# Timer.net
KiCad netlist of a schematic drawn in EAGLE
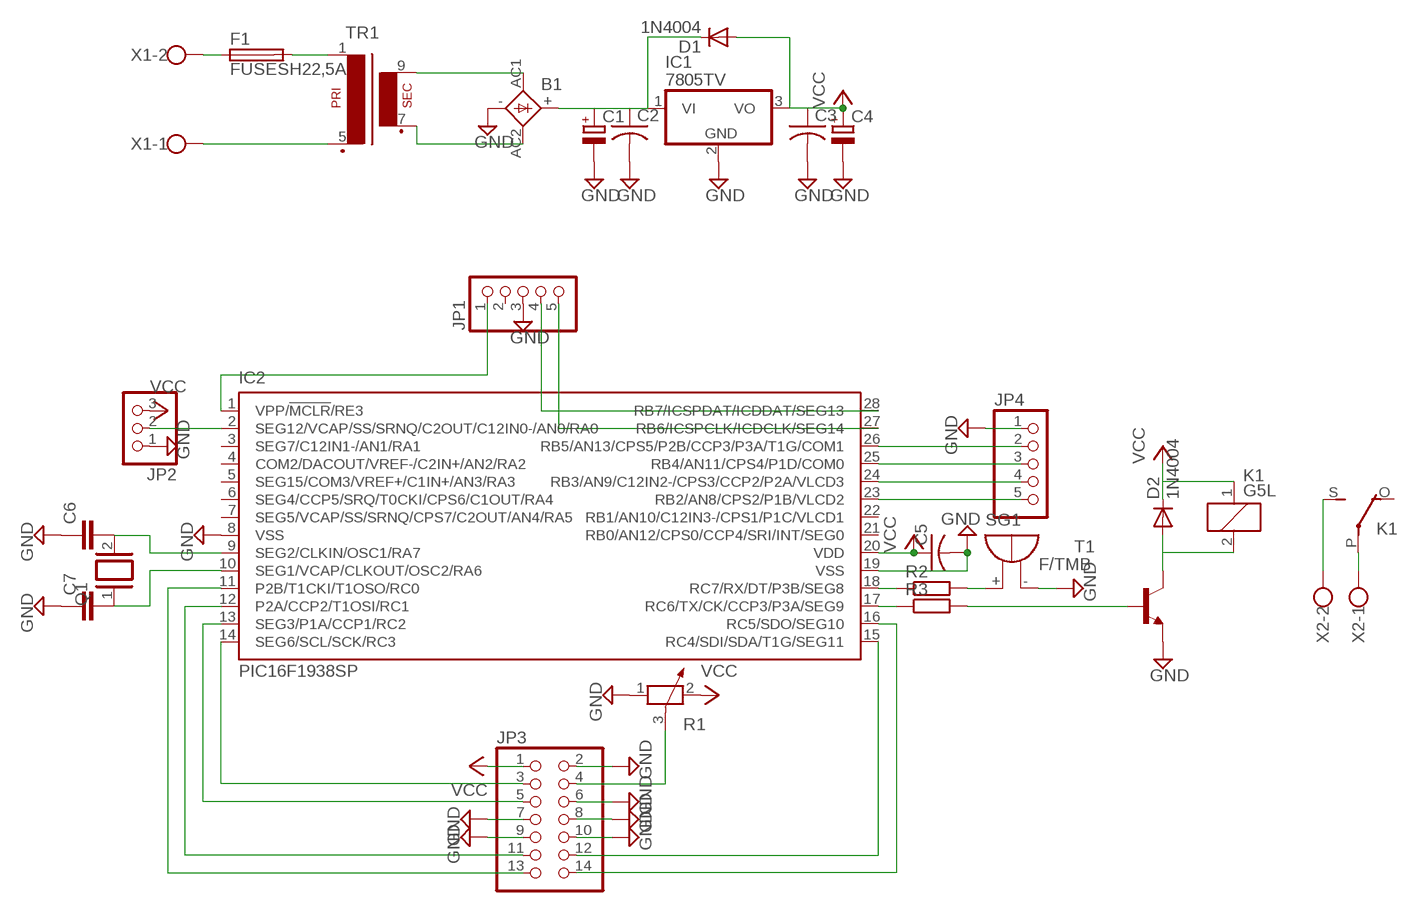
[diagram p0: schematic, sheet 1]

(export (version "E")
  (design (tool "Eeschema 10.0.6"))
  (components
    (comp (ref "B1")
      (value "1KAB")
      (footprint "eagle-import:1KAB")
      (libsource (lib "eagle-import") (part "1KAB"))
    )
    (comp (ref "C1")
      (value "CPOL-EUE5-13")
      (footprint "eagle-import:E5-13")
      (libsource (lib "eagle-import") (part "resistor_CPOL-EUE5-13"))
    )
    (comp (ref "C2")
      (value "C-US050-030X075")
      (footprint "eagle-import:C050-030X075")
      (libsource (lib "eagle-import") (part "C-US050-030X075"))
    )
    (comp (ref "C3")
      (value "C-US050-030X075")
      (footprint "eagle-import:C050-030X075")
      (libsource (lib "eagle-import") (part "C-US050-030X075"))
    )
    (comp (ref "C4")
      (value "CPOL-EUE3.5-8")
      (footprint "eagle-import:E3,5-8")
      (libsource (lib "eagle-import") (part "CPOL-EUE3.5-8"))
    )
    (comp (ref "C5")
      (value "C-US050-030X075")
      (footprint "eagle-import:C050-030X075")
      (libsource (lib "eagle-import") (part "C-US050-030X075"))
    )
    (comp (ref "C6")
      (value "C2,5-3")
      (footprint "eagle-import:C2.5-3")
      (libsource (lib "eagle-import") (part "C2,5-3"))
    )
    (comp (ref "C7")
      (value "C2,5-3")
      (footprint "eagle-import:C2.5-3")
      (libsource (lib "eagle-import") (part "C2,5-3"))
    )
    (comp (ref "D1")
      (value "1N4004")
      (footprint "eagle-import:DO41-10")
      (libsource (lib "eagle-import") (part "1N4004"))
    )
    (comp (ref "D2")
      (value "1N4004")
      (footprint "eagle-import:DO41-10")
      (libsource (lib "eagle-import") (part "1N4004"))
    )
    (comp (ref "F1")
      (value "FUSESH22,5A")
      (footprint "eagle-import:SH22,5A")
      (libsource (lib "eagle-import") (part "FUSESH22,5A"))
    )
    (comp (ref "IC1")
      (value "7805TV")
      (footprint "eagle-import:TO220V")
      (libsource (lib "eagle-import") (part "78TV05"))
    )
    (comp (ref "IC2")
      (value "PIC16F1938SP")
      (footprint "eagle-import:DIL28-3")
      (fields (field (name "MPN") "PIC16F1938-I/SP"))
      (libsource (lib "eagle-import") (part "PIC16F19SP38"))
    )
    (comp (ref "JP1")
      (value "PINHD-1X5")
      (footprint "eagle-import:1X05")
      (libsource (lib "eagle-import") (part "PINHD-1X5"))
    )
    (comp (ref "JP2")
      (value "PINHD-1X3")
      (footprint "eagle-import:1X03")
      (libsource (lib "eagle-import") (part "PINHD-1X3"))
    )
    (comp (ref "JP3")
      (value "PINHD-2X7")
      (footprint "eagle-import:2X07")
      (libsource (lib "eagle-import") (part "PINHD-2X7"))
    )
    (comp (ref "JP4")
      (value "PINHD-1X5")
      (footprint "eagle-import:1X05")
      (libsource (lib "eagle-import") (part "PINHD-1X5"))
    )
    (comp (ref "K1")
      (value "G5L")
      (footprint "eagle-import:G5LE")
      (libsource (lib "eagle-import") (part "G5L"))
    )
    (comp (ref "Q1")
      (value "XTAL/S")
      (footprint "eagle-import:QS")
      (libsource (lib "eagle-import") (part "XTAL/S"))
    )
    (comp (ref "R1")
      (value "POTENTIOMETER_PT-10")
      (footprint "eagle-import:PT-10")
      (libsource (lib "eagle-import") (part "POTENTIOMETER_PT-10"))
    )
    (comp (ref "R2")
      (value "R-EU_0207/10")
      (footprint "eagle-import:0207_10")
      (libsource (lib "eagle-import") (part "R-EU_0207/10"))
    )
    (comp (ref "R3")
      (value "R-EU_0207/10")
      (footprint "eagle-import:0207_10")
      (libsource (lib "eagle-import") (part "R-EU_0207/10"))
    )
    (comp (ref "SG1")
      (value "F/TMB")
      (footprint "eagle-import:F_TMB")
      (libsource (lib "eagle-import") (part "F/TMB"))
    )
    (comp (ref "T1")
      (value "BC547-NPN-TO92-CBE")
      (footprint "eagle-import:TO92-CBE")
      (libsource (lib "eagle-import") (part "-NPN-TO92-CBEBC547"))
    )
    (comp (ref "TR1")
      (value "VV11")
      (footprint "eagle-import:VV11")
      (libsource (lib "eagle-import") (part "VV11"))
    )
    (comp (ref "X1")
      (value "W237-102")
      (footprint "eagle-import:W237-102")
      (fields (field (name "MPN") "237-102"))
      (libsource (lib "eagle-import") (part "W237-102"))
    )
    (comp (ref "X2")
      (value "W237-102")
      (footprint "eagle-import:W237-102")
      (fields (field (name "MPN") "237-102"))
      (libsource (lib "eagle-import") (part "W237-102"))
    )
  )
  (nets
    (net (code "1") (name "GND") (class "Default")
      (node (ref "B1") (pin "-") (pinfunction "-_-") (pintype "passive"))
      (node (ref "C1") (pin "-") (pinfunction "-_-") (pintype "passive"))
      (node (ref "C2") (pin "2") (pinfunction "2_2") (pintype "passive"))
      (node (ref "C3") (pin "2") (pinfunction "2_2") (pintype "passive"))
      (node (ref "C4") (pin "-") (pinfunction "-_-") (pintype "passive"))
      (node (ref "C5") (pin "2") (pinfunction "2_2") (pintype "passive"))
      (node (ref "C6") (pin "1") (pinfunction "1_1") (pintype "passive"))
      (node (ref "C7") (pin "1") (pinfunction "1_1") (pintype "passive"))
      (node (ref "IC1") (pin "2") (pinfunction "GND_2") (pintype "passive"))
      (node (ref "IC2") (pin "19") (pinfunction "VSS_19") (pintype "power_in"))
      (node (ref "IC2") (pin "8") (pinfunction "VSS_8") (pintype "power_in"))
      (node (ref "JP1") (pin "3") (pinfunction "3_3") (pintype "passive"))
      (node (ref "JP2") (pin "1") (pinfunction "1_1") (pintype "passive"))
      (node (ref "JP3") (pin "10") (pinfunction "10_10") (pintype "passive"))
      (node (ref "JP3") (pin "2") (pinfunction "2_2") (pintype "passive"))
      (node (ref "JP3") (pin "6") (pinfunction "6_6") (pintype "passive"))
      (node (ref "JP3") (pin "7") (pinfunction "7_7") (pintype "passive"))
      (node (ref "JP3") (pin "8") (pinfunction "8_8") (pintype "passive"))
      (node (ref "JP3") (pin "9") (pinfunction "9_9") (pintype "passive"))
      (node (ref "JP4") (pin "1") (pinfunction "1_1") (pintype "passive"))
      (node (ref "R1") (pin "1") (pinfunction "1_1") (pintype "passive"))
      (node (ref "SG1") (pin "-") (pinfunction "-_-") (pintype "passive"))
      (node (ref "T1") (pin "E") (pinfunction "E_E") (pintype "passive"))
    )
    (net (code "2") (name "Net-(D2-PadA)") (class "Default")
      (node (ref "D2") (pin "A") (pinfunction "A_A") (pintype "passive"))
      (node (ref "K1") (pin "2") (pinfunction "2_2") (pintype "passive"))
      (node (ref "T1") (pin "C") (pinfunction "C_C") (pintype "passive"))
    )
    (net (code "3") (name "Net-(IC1-VI)") (class "Default")
      (node (ref "B1") (pin "+") (pinfunction "+_+") (pintype "passive"))
      (node (ref "C1") (pin "+") (pinfunction "+_+") (pintype "passive"))
      (node (ref "C2") (pin "1") (pinfunction "1_1") (pintype "passive"))
      (node (ref "D1") (pin "C") (pinfunction "C_C") (pintype "passive"))
      (node (ref "IC1") (pin "1") (pinfunction "VI_1") (pintype "input"))
    )
    (net (code "4") (name "Net-(IC2-P2A{slash}CCP2{slash}T1OSI{slash}RC1)") (class "Default")
      (node (ref "IC2") (pin "12") (pinfunction "P2A/CCP2/T1OSI/RC1_12") (pintype "bidirectional"))
      (node (ref "JP3") (pin "11") (pinfunction "11_11") (pintype "passive"))
    )
    (net (code "5") (name "Net-(IC2-P2B{slash}T1CKI{slash}T1OSO{slash}RC0)") (class "Default")
      (node (ref "IC2") (pin "11") (pinfunction "P2B/T1CKI/T1OSO/RC0_11") (pintype "bidirectional"))
      (node (ref "JP3") (pin "13") (pinfunction "13_13") (pintype "passive"))
    )
    (net (code "6") (name "Net-(IC2-RB2{slash}AN8{slash}CPS2{slash}P1B{slash}VLCD2)") (class "Default")
      (node (ref "IC2") (pin "23") (pinfunction "RB2/AN8/CPS2/P1B/VLCD2_23") (pintype "bidirectional"))
      (node (ref "JP4") (pin "5") (pinfunction "5_5") (pintype "passive"))
    )
    (net (code "7") (name "Net-(IC2-RB3{slash}AN9{slash}C12IN2-{slash}CPS3{slash}CCP2{slash}P2A{slash}VLCD3)") (class "Default")
      (node (ref "IC2") (pin "24") (pinfunction "RB3/AN9/C12IN2-/CPS3/CCP2/P2A/VLCD3_24") (pintype "bidirectional"))
      (node (ref "JP4") (pin "4") (pinfunction "4_4") (pintype "passive"))
    )
    (net (code "8") (name "Net-(IC2-RB4{slash}AN11{slash}CPS4{slash}P1D{slash}COM0)") (class "Default")
      (node (ref "IC2") (pin "25") (pinfunction "RB4/AN11/CPS4/P1D/COM0_25") (pintype "bidirectional"))
      (node (ref "JP4") (pin "3") (pinfunction "3_3") (pintype "passive"))
    )
    (net (code "9") (name "Net-(IC2-RB5{slash}AN13{slash}CPS5{slash}P2B{slash}CCP3{slash}P3A{slash}T1G{slash}COM1)") (class "Default")
      (node (ref "IC2") (pin "26") (pinfunction "RB5/AN13/CPS5/P2B/CCP3/P3A/T1G/COM1_26") (pintype "bidirectional"))
      (node (ref "JP4") (pin "2") (pinfunction "2_2") (pintype "passive"))
    )
    (net (code "10") (name "Net-(IC2-RB6{slash}ICSPCLK{slash}ICDCLK{slash}SEG14)") (class "Default")
      (node (ref "IC2") (pin "27") (pinfunction "RB6/ICSPCLK/ICDCLK/SEG14_27") (pintype "bidirectional"))
      (node (ref "JP1") (pin "5") (pinfunction "5_5") (pintype "passive"))
    )
    (net (code "11") (name "Net-(IC2-RB7{slash}ICSPDAT{slash}ICDDAT{slash}SEG13)") (class "Default")
      (node (ref "IC2") (pin "28") (pinfunction "RB7/ICSPDAT/ICDDAT/SEG13_28") (pintype "bidirectional"))
      (node (ref "JP1") (pin "4") (pinfunction "4_4") (pintype "passive"))
    )
    (net (code "12") (name "Net-(IC2-RC4{slash}SDI{slash}SDA{slash}T1G{slash}SEG11)") (class "Default")
      (node (ref "IC2") (pin "15") (pinfunction "RC4/SDI/SDA/T1G/SEG11_15") (pintype "bidirectional"))
      (node (ref "JP3") (pin "12") (pinfunction "12_12") (pintype "passive"))
    )
    (net (code "13") (name "Net-(IC2-RC5{slash}SDO{slash}SEG10)") (class "Default")
      (node (ref "IC2") (pin "16") (pinfunction "RC5/SDO/SEG10_16") (pintype "bidirectional"))
      (node (ref "JP3") (pin "14") (pinfunction "14_14") (pintype "passive"))
    )
    (net (code "14") (name "Net-(IC2-RC6{slash}TX{slash}CK{slash}CCP3{slash}P3A{slash}SEG9)") (class "Default")
      (node (ref "IC2") (pin "17") (pinfunction "RC6/TX/CK/CCP3/P3A/SEG9_17") (pintype "bidirectional"))
      (node (ref "R3") (pin "1") (pinfunction "1_1") (pintype "passive"))
    )
    (net (code "15") (name "Net-(IC2-RC7{slash}RX{slash}DT{slash}P3B{slash}SEG8)") (class "Default")
      (node (ref "IC2") (pin "18") (pinfunction "RC7/RX/DT/P3B/SEG8_18") (pintype "bidirectional"))
      (node (ref "R2") (pin "1") (pinfunction "1_1") (pintype "passive"))
    )
    (net (code "16") (name "Net-(IC2-SEG1{slash}VCAP{slash}CLKOUT{slash}OSC2{slash}RA6)") (class "Default")
      (node (ref "C7") (pin "2") (pinfunction "2_2") (pintype "passive"))
      (node (ref "IC2") (pin "10") (pinfunction "SEG1/VCAP/CLKOUT/OSC2/RA6_10") (pintype "bidirectional"))
      (node (ref "Q1") (pin "1") (pinfunction "1_1") (pintype "passive"))
    )
    (net (code "17") (name "Net-(IC2-SEG2{slash}CLKIN{slash}OSC1{slash}RA7)") (class "Default")
      (node (ref "C6") (pin "2") (pinfunction "2_2") (pintype "passive"))
      (node (ref "IC2") (pin "9") (pinfunction "SEG2/CLKIN/OSC1/RA7_9") (pintype "bidirectional"))
      (node (ref "Q1") (pin "2") (pinfunction "2_2") (pintype "passive"))
    )
    (net (code "18") (name "Net-(IC2-SEG3{slash}P1A{slash}CCP1{slash}RC2)") (class "Default")
      (node (ref "IC2") (pin "13") (pinfunction "SEG3/P1A/CCP1/RC2_13") (pintype "bidirectional"))
      (node (ref "JP3") (pin "5") (pinfunction "5_5") (pintype "passive"))
    )
    (net (code "19") (name "Net-(IC2-SEG6{slash}SCL{slash}SCK{slash}RC3)") (class "Default")
      (node (ref "IC2") (pin "14") (pinfunction "SEG6/SCL/SCK/RC3_14") (pintype "bidirectional"))
      (node (ref "JP3") (pin "3") (pinfunction "3_3") (pintype "passive"))
    )
    (net (code "20") (name "Net-(IC2-SEG12{slash}VCAP{slash}SS{slash}SRNQ{slash}C2OUT{slash}C12IN0-{slash}AN0{slash}RA0)") (class "Default")
      (node (ref "IC2") (pin "2") (pinfunction "SEG12/VCAP/SS/SRNQ/C2OUT/C12IN0-/AN0/RA0_2") (pintype "bidirectional"))
      (node (ref "JP2") (pin "2") (pinfunction "2_2") (pintype "passive"))
    )
    (net (code "21") (name "Net-(IC2-VPP{slash}~{MCLR}{slash}RE3)") (class "Default")
      (node (ref "IC2") (pin "1") (pinfunction "VPP/~{MCLR}/RE3_1") (pintype "input"))
      (node (ref "JP1") (pin "1") (pinfunction "1_1") (pintype "passive"))
    )
    (net (code "22") (name "Net-(JP3-Pad4)") (class "Default")
      (node (ref "JP3") (pin "4") (pinfunction "4_4") (pintype "passive"))
      (node (ref "R1") (pin "3") (pinfunction "3_3") (pintype "passive"))
    )
    (net (code "23") (name "Net-(R2-Pad2)") (class "Default")
      (node (ref "R2") (pin "2") (pinfunction "2_2") (pintype "passive"))
      (node (ref "SG1") (pin "+") (pinfunction "+_+") (pintype "passive"))
    )
    (net (code "24") (name "Net-(R3-Pad2)") (class "Default")
      (node (ref "R3") (pin "2") (pinfunction "2_2") (pintype "passive"))
      (node (ref "T1") (pin "B") (pinfunction "B_B") (pintype "passive"))
    )
    (net (code "25") (name "Net-(TR1-P1)") (class "Default")
      (node (ref "F1") (pin "2") (pinfunction "2_2") (pintype "passive"))
      (node (ref "TR1") (pin "1") (pinfunction "P1_1") (pintype "passive"))
    )
    (net (code "26") (name "Net-(TR1-P2)") (class "Default")
      (node (ref "TR1") (pin "5") (pinfunction "P2_5") (pintype "passive"))
      (node (ref "X1") (pin "1") (pinfunction "KL_1") (pintype "passive"))
    )
    (net (code "27") (name "Net-(TR1-S3)") (class "Default")
      (node (ref "B1") (pin "AC2") (pinfunction "AC2_AC2") (pintype "passive"))
      (node (ref "TR1") (pin "7") (pinfunction "S3_7") (pintype "passive"))
    )
    (net (code "28") (name "Net-(TR1-S4)") (class "Default")
      (node (ref "B1") (pin "AC1") (pinfunction "AC1_AC1") (pintype "passive"))
      (node (ref "TR1") (pin "9") (pinfunction "S4_9") (pintype "passive"))
    )
    (net (code "29") (name "Net-(X1B-KL)") (class "Default")
      (node (ref "F1") (pin "1") (pinfunction "1_1") (pintype "passive"))
      (node (ref "X1") (pin "2") (pinfunction "KL_2") (pintype "passive"))
    )
    (net (code "30") (name "Net-(X2A-KL)") (class "Default")
      (node (ref "K1") (pin "P") (pinfunction "P_P") (pintype "passive"))
      (node (ref "X2") (pin "1") (pinfunction "KL_1") (pintype "passive"))
    )
    (net (code "31") (name "Net-(X2B-KL)") (class "Default")
      (node (ref "K1") (pin "S") (pinfunction "S_S") (pintype "passive"))
      (node (ref "X2") (pin "2") (pinfunction "KL_2") (pintype "passive"))
    )
    (net (code "32") (name "VCC") (class "Default")
      (node (ref "C3") (pin "1") (pinfunction "1_1") (pintype "passive"))
      (node (ref "C4") (pin "+") (pinfunction "+_+") (pintype "passive"))
      (node (ref "C5") (pin "1") (pinfunction "1_1") (pintype "passive"))
      (node (ref "D1") (pin "A") (pinfunction "A_A") (pintype "passive"))
      (node (ref "D2") (pin "C") (pinfunction "C_C") (pintype "passive"))
      (node (ref "IC1") (pin "3") (pinfunction "VO_3") (pintype "passive"))
      (node (ref "IC2") (pin "20") (pinfunction "VDD_20") (pintype "power_in"))
      (node (ref "JP2") (pin "3") (pinfunction "3_3") (pintype "passive"))
      (node (ref "JP3") (pin "1") (pinfunction "1_1") (pintype "passive"))
      (node (ref "K1") (pin "1") (pinfunction "1_1") (pintype "passive"))
      (node (ref "R1") (pin "2") (pinfunction "2_2") (pintype "passive"))
    )
    (net (code "33") (name "unconnected-(IC2-COM2{slash}DACOUT{slash}VREF-{slash}C2IN+{slash}AN2{slash}RA2-Pad4)") (class "Default")
      (node (ref "IC2") (pin "4") (pinfunction "COM2/DACOUT/VREF-/C2IN+/AN2/RA2_4") (pintype "bidirectional"))
    )
    (net (code "34") (name "unconnected-(IC2-RB0{slash}AN12{slash}CPS0{slash}CCP4{slash}SRI{slash}INT{slash}SEG0-Pad21)") (class "Default")
      (node (ref "IC2") (pin "21") (pinfunction "RB0/AN12/CPS0/CCP4/SRI/INT/SEG0_21") (pintype "bidirectional"))
    )
    (net (code "35") (name "unconnected-(IC2-RB1{slash}AN10{slash}C12IN3-{slash}CPS1{slash}P1C{slash}VLCD1-Pad22)") (class "Default")
      (node (ref "IC2") (pin "22") (pinfunction "RB1/AN10/C12IN3-/CPS1/P1C/VLCD1_22") (pintype "bidirectional"))
    )
    (net (code "36") (name "unconnected-(IC2-SEG4{slash}CCP5{slash}SRQ{slash}T0CKI{slash}CPS6{slash}C1OUT{slash}RA4-Pad6)") (class "Default")
      (node (ref "IC2") (pin "6") (pinfunction "SEG4/CCP5/SRQ/T0CKI/CPS6/C1OUT/RA4_6") (pintype "bidirectional"))
    )
    (net (code "37") (name "unconnected-(IC2-SEG5{slash}VCAP{slash}SS{slash}SRNQ{slash}CPS7{slash}C2OUT{slash}AN4{slash}RA5-Pad7)") (class "Default")
      (node (ref "IC2") (pin "7") (pinfunction "SEG5/VCAP/SS/SRNQ/CPS7/C2OUT/AN4/RA5_7") (pintype "bidirectional"))
    )
    (net (code "38") (name "unconnected-(IC2-SEG7{slash}C12IN1-{slash}AN1{slash}RA1-Pad3)") (class "Default")
      (node (ref "IC2") (pin "3") (pinfunction "SEG7/C12IN1-/AN1/RA1_3") (pintype "bidirectional"))
    )
    (net (code "39") (name "unconnected-(IC2-SEG15{slash}COM3{slash}VREF+{slash}C1IN+{slash}AN3{slash}RA3-Pad5)") (class "Default")
      (node (ref "IC2") (pin "5") (pinfunction "SEG15/COM3/VREF+/C1IN+/AN3/RA3_5") (pintype "bidirectional"))
    )
    (net (code "40") (name "unconnected-(JP1-Pad2)") (class "Default")
      (node (ref "JP1") (pin "2") (pinfunction "2_2") (pintype "passive"))
    )
    (net (code "41") (name "unconnected-(K1-PadO)") (class "Default")
      (node (ref "K1") (pin "O") (pinfunction "O_O") (pintype "passive"))
    )
  )
)
